# 16V3_EDA.net
KiCad netlist of a schematic drawn in EasyEDA Pro
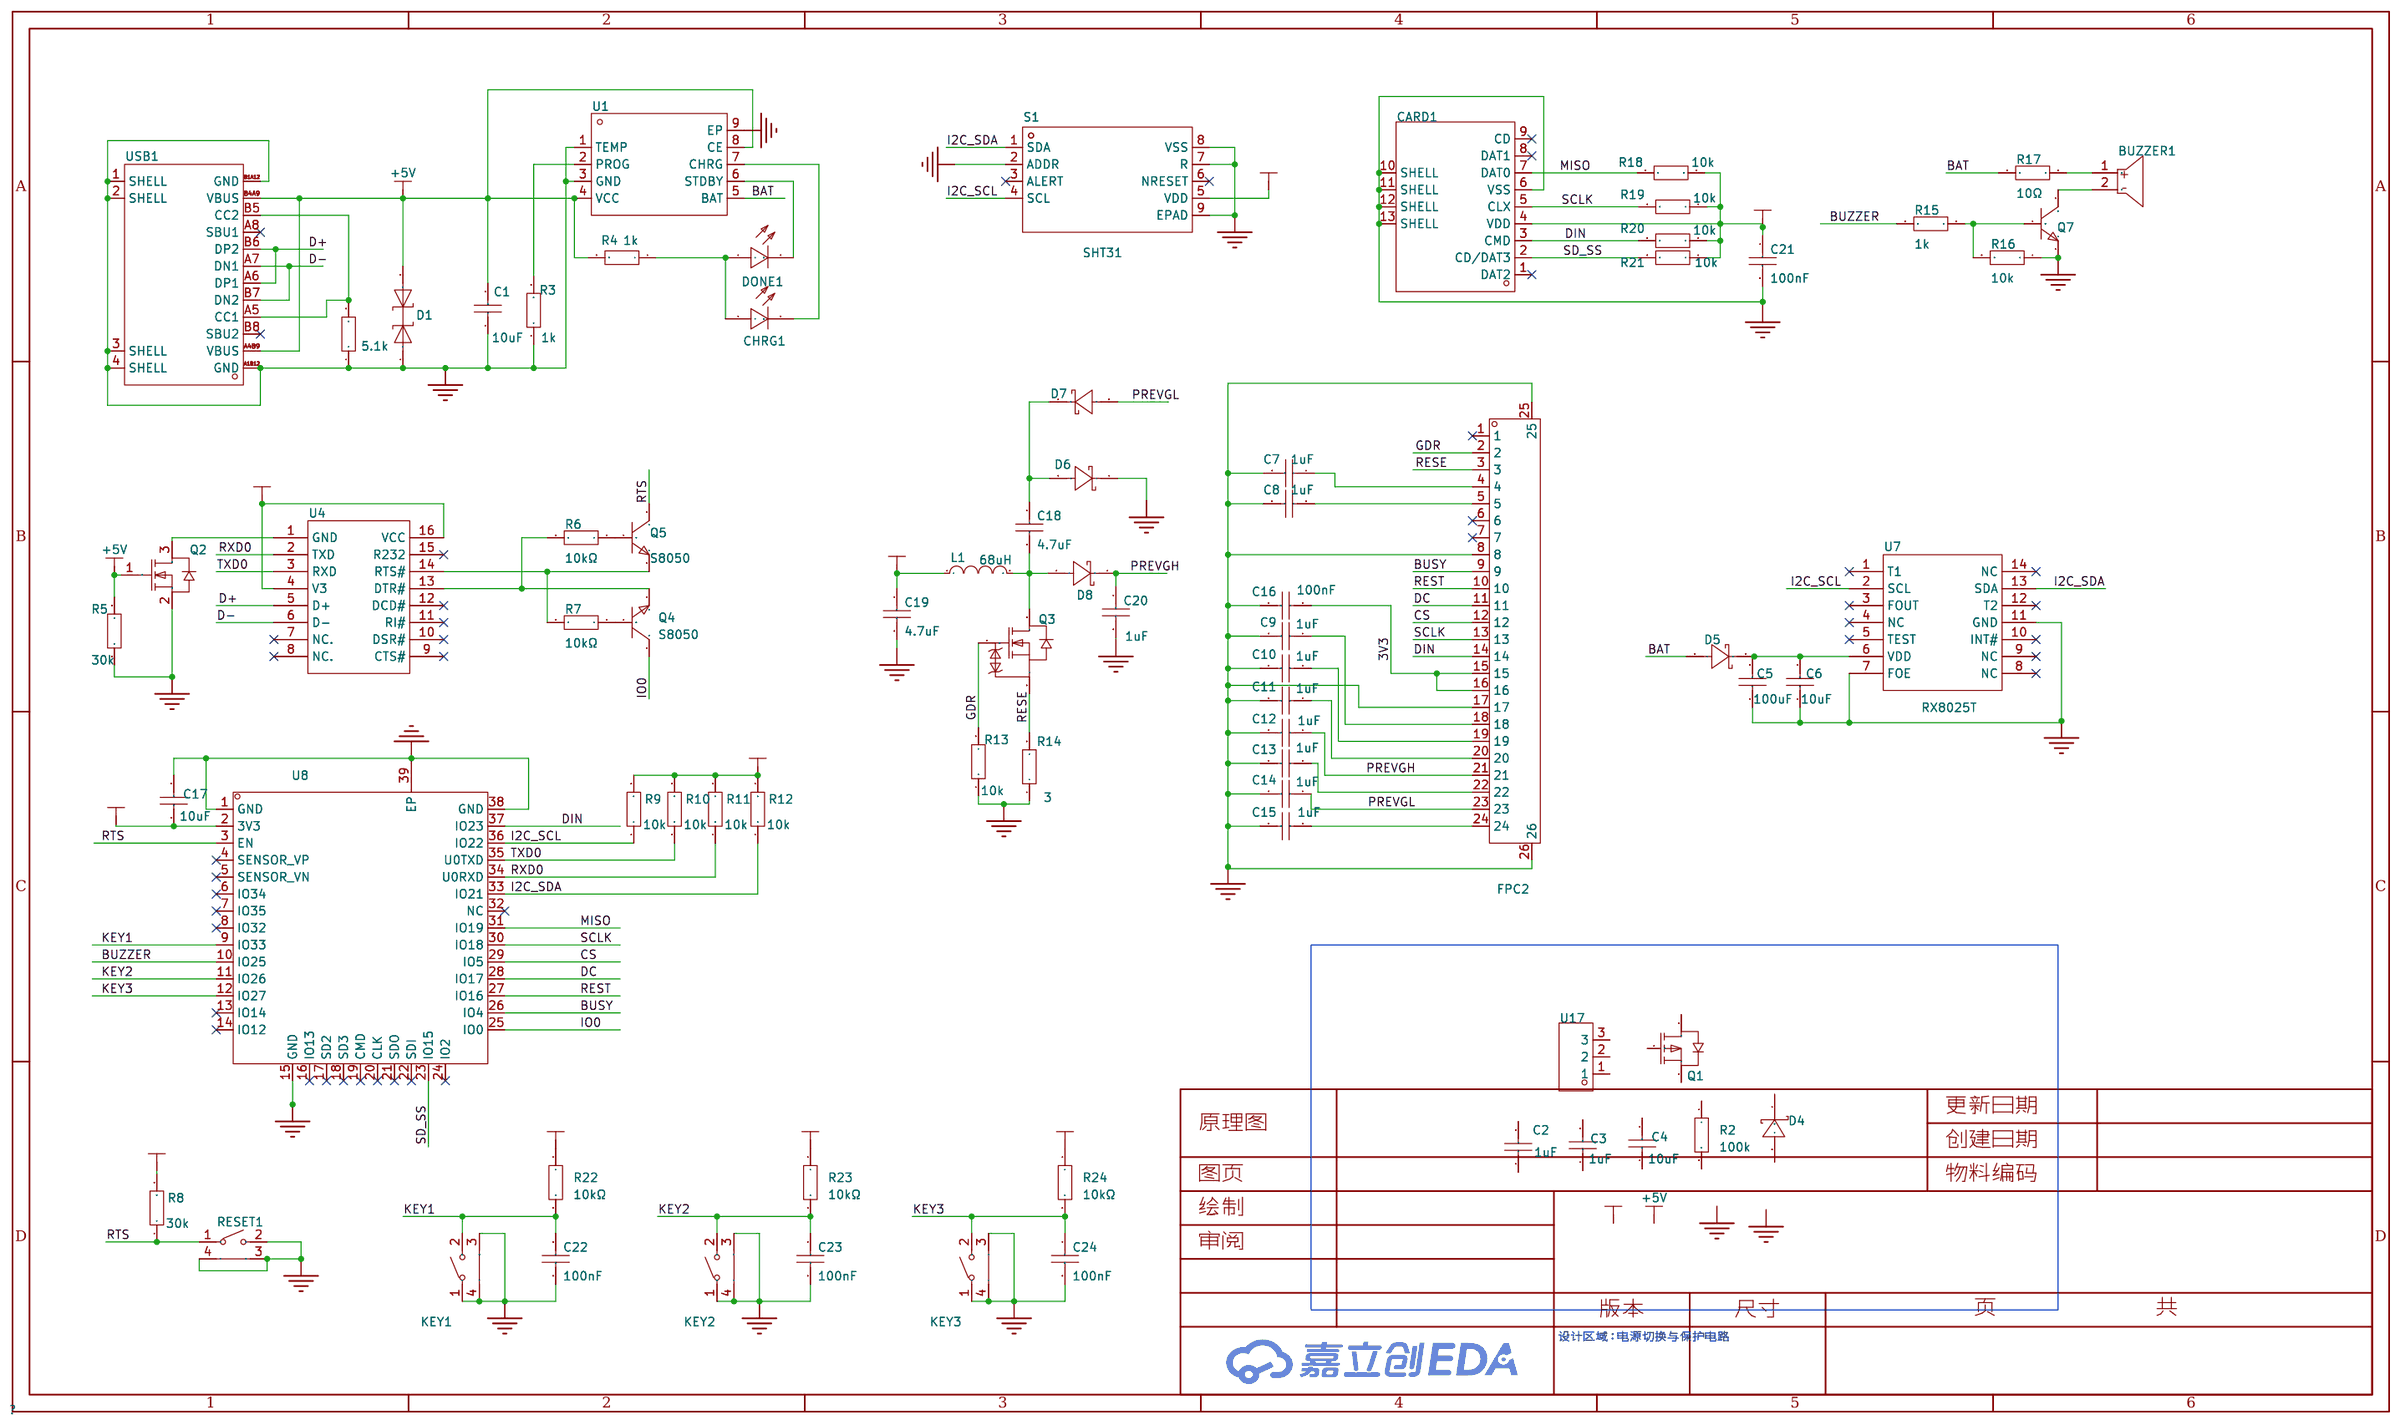
[diagram p0: schematic sheet]

(export (version "E")
  (design (tool "Eeschema 10.0.6"))
  (components
    (comp (ref "BUZZER1")
      (value "FMQ-BUZZER2")
      (footprint "easyedapro:BUZ-TH_BD12.0-P7.60-D0.6-FD")
      (libsource (lib "easyedapro") (part "FMQ-BUZZER2"))
    )
    (comp (ref "C1")
      (value "10uF")
      (footprint "easyedapro:C0805")
      (fields
        (field (name "Manufacturer Part") "CC0805KRX7R9BB104")
        (field (name "Manufacturer") "YAGEO(国巨)")
      )
      (libsource (lib "easyedapro") (part "CC0805KRX7R9BB104"))
    )
    (comp (ref "C2")
      (value "1uF")
      (footprint "easyedapro:C0805")
      (fields
        (field (name "Manufacturer Part") "CC0805KRX7R9BB104")
        (field (name "Manufacturer") "YAGEO(国巨)")
      )
      (libsource (lib "easyedapro") (part "CC0805KRX7R9BB104"))
    )
    (comp (ref "C3")
      (value "1uF")
      (footprint "easyedapro:C0805")
      (fields
        (field (name "Manufacturer Part") "CC0805KRX7R9BB104")
        (field (name "Manufacturer") "YAGEO(国巨)")
      )
      (libsource (lib "easyedapro") (part "CC0805KRX7R9BB104"))
    )
    (comp (ref "C4")
      (value "10uF")
      (footprint "easyedapro:C0805")
      (fields
        (field (name "Manufacturer Part") "CC0805KRX7R9BB104")
        (field (name "Manufacturer") "YAGEO(国巨)")
      )
      (libsource (lib "easyedapro") (part "CC0805KRX7R9BB104"))
    )
    (comp (ref "C5")
      (value "100uF")
      (footprint "easyedapro:C0805")
      (description "容值:100nF;精度:±10%;额定电压:50V;温度系数:X7R;")
      (fields
        (field (name "Manufacturer Part") "CC0805KRX7R9BB104")
        (field (name "Manufacturer") "YAGEO(国巨)")
      )
      (libsource (lib "easyedapro") (part "CC0805KRX7R9BB104"))
    )
    (comp (ref "C6")
      (value "10uF")
      (footprint "easyedapro:C0805")
      (fields
        (field (name "Manufacturer Part") "CC0805KRX7R9BB104")
        (field (name "Manufacturer") "YAGEO(国巨)")
      )
      (libsource (lib "easyedapro") (part "CC0805KRX7R9BB104"))
    )
    (comp (ref "C7")
      (value "1uF")
      (footprint "easyedapro:C0805")
      (fields
        (field (name "Manufacturer Part") "CC0805KRX7R9BB104")
        (field (name "Manufacturer") "YAGEO(国巨)")
      )
      (libsource (lib "easyedapro") (part "CC0805KRX7R9BB104"))
    )
    (comp (ref "C8")
      (value "1uF")
      (footprint "easyedapro:C0805")
      (fields
        (field (name "Manufacturer Part") "CC0805KRX7R9BB104")
        (field (name "Manufacturer") "YAGEO(国巨)")
      )
      (libsource (lib "easyedapro") (part "CC0805KRX7R9BB104"))
    )
    (comp (ref "C9")
      (value "1uF")
      (footprint "easyedapro:C0805")
      (fields
        (field (name "Manufacturer Part") "CC0805KRX7R9BB104")
        (field (name "Manufacturer") "YAGEO(国巨)")
      )
      (libsource (lib "easyedapro") (part "CC0805KRX7R9BB104"))
    )
    (comp (ref "C10")
      (value "1uF")
      (footprint "easyedapro:C0805")
      (fields
        (field (name "Manufacturer Part") "CC0805KRX7R9BB104")
        (field (name "Manufacturer") "YAGEO(国巨)")
      )
      (libsource (lib "easyedapro") (part "CC0805KRX7R9BB104"))
    )
    (comp (ref "C11")
      (value "1uF")
      (footprint "easyedapro:C0805")
      (fields
        (field (name "Manufacturer Part") "CC0805KRX7R9BB104")
        (field (name "Manufacturer") "YAGEO(国巨)")
      )
      (libsource (lib "easyedapro") (part "CC0805KRX7R9BB104"))
    )
    (comp (ref "C12")
      (value "1uF")
      (footprint "easyedapro:C0805")
      (fields
        (field (name "Manufacturer Part") "CC0805KRX7R9BB104")
        (field (name "Manufacturer") "YAGEO(国巨)")
      )
      (libsource (lib "easyedapro") (part "CC0805KRX7R9BB104"))
    )
    (comp (ref "C13")
      (value "1uF")
      (footprint "easyedapro:C0805")
      (fields
        (field (name "Manufacturer Part") "CC0805KRX7R9BB104")
        (field (name "Manufacturer") "YAGEO(国巨)")
      )
      (libsource (lib "easyedapro") (part "CC0805KRX7R9BB104"))
    )
    (comp (ref "C14")
      (value "1uF")
      (footprint "easyedapro:C0805")
      (fields
        (field (name "Manufacturer Part") "CC0805KRX7R9BB104")
        (field (name "Manufacturer") "YAGEO(国巨)")
      )
      (libsource (lib "easyedapro") (part "CC0805KRX7R9BB104"))
    )
    (comp (ref "C15")
      (value "1uF")
      (footprint "easyedapro:C0805")
      (fields
        (field (name "Manufacturer Part") "CC0805KRX7R9BB104")
        (field (name "Manufacturer") "YAGEO(国巨)")
      )
      (libsource (lib "easyedapro") (part "CC0805KRX7R9BB104"))
    )
    (comp (ref "C16")
      (value "100nF")
      (footprint "easyedapro:C0805")
      (description "容值:100nF;精度:±10%;额定电压:50V;温度系数:X7R;")
      (fields
        (field (name "Manufacturer Part") "CC0805KRX7R9BB104")
        (field (name "Manufacturer") "YAGEO(国巨)")
      )
      (libsource (lib "easyedapro") (part "CC0805KRX7R9BB104"))
    )
    (comp (ref "C17")
      (value "10uF")
      (footprint "easyedapro:C0805")
      (fields
        (field (name "Manufacturer Part") "CC0805KRX7R9BB104")
        (field (name "Manufacturer") "YAGEO(国巨)")
      )
      (libsource (lib "easyedapro") (part "CC0805KRX7R9BB104"))
    )
    (comp (ref "C18")
      (value "4.7uF")
      (footprint "easyedapro:C0805")
      (description "容值:100nF;精度:±10%;额定电压:50V;温度系数:X7R;")
      (fields
        (field (name "Manufacturer Part") "CC0805KRX7R9BB104")
        (field (name "Manufacturer") "YAGEO(国巨)")
      )
      (libsource (lib "easyedapro") (part "CC0805KRX7R9BB104"))
    )
    (comp (ref "C19")
      (value "4.7uF")
      (footprint "easyedapro:C0805")
      (fields
        (field (name "Manufacturer Part") "CC0805KRX7R9BB104")
        (field (name "Manufacturer") "YAGEO(国巨)")
      )
      (libsource (lib "easyedapro") (part "CC0805KRX7R9BB104"))
    )
    (comp (ref "C20")
      (value "1uF")
      (footprint "easyedapro:C0805")
      (fields
        (field (name "Manufacturer Part") "CC0805KRX7R9BB104")
        (field (name "Manufacturer") "YAGEO(国巨)")
      )
      (libsource (lib "easyedapro") (part "CC0805KRX7R9BB104"))
    )
    (comp (ref "C21")
      (value "100nF")
      (footprint "easyedapro:C0805")
      (description "容值:100nF;精度:±10%;额定电压:50V;温度系数:X7R;")
      (fields
        (field (name "Manufacturer Part") "CC0805KRX7R9BB104")
        (field (name "Manufacturer") "YAGEO(国巨)")
      )
      (libsource (lib "easyedapro") (part "CC0805KRX7R9BB104"))
    )
    (comp (ref "C22")
      (value "100nF")
      (footprint "easyedapro:C0805")
      (fields
        (field (name "Manufacturer Part") "CC0805KRX7R9BB104")
        (field (name "Manufacturer") "YAGEO(国巨)")
      )
      (libsource (lib "easyedapro") (part "CC0805KRX7R9BB104"))
    )
    (comp (ref "C23")
      (value "100nF")
      (footprint "easyedapro:C0805")
      (fields
        (field (name "Manufacturer Part") "CC0805KRX7R9BB104")
        (field (name "Manufacturer") "YAGEO(国巨)")
      )
      (libsource (lib "easyedapro") (part "CC0805KRX7R9BB104"))
    )
    (comp (ref "C24")
      (value "100nF")
      (footprint "easyedapro:C0805")
      (fields
        (field (name "Manufacturer Part") "CC0805KRX7R9BB104")
        (field (name "Manufacturer") "YAGEO(国巨)")
      )
      (libsource (lib "easyedapro") (part "CC0805KRX7R9BB104"))
    )
    (comp (ref "CARD1")
      (value "~")
      (footprint "easyedapro:TF-SMD_THD2528-11SD-GF")
      (description "卡连接方式:自弹式;卡类型:MicroSD卡(TF卡);连接器类型:卡座;本体最大高度:2mm;工作温度范围:-;")
      (fields (field (name "Manufacturer Part") "THD2528-11SD-GF") (field (name "Manufacturer") "THD(台华达)"))
      (libsource (lib "easyedapro") (part "THD2528-11SD-GF"))
    )
    (comp (ref "CHRG1")
      (value "~")
      (footprint "easyedapro:LED0603-R-RD")
      (fields
        (field (name "Manufacturer Part") "19-217/R6C-AL1M2VY/3T")
        (field (name "Manufacturer") "EVERLIGHT(台湾亿光)")
      )
      (libsource (lib "easyedapro") (part "19-217/R6C-AL1M2VY/3T"))
    )
    (comp (ref "D1")
      (value "~")
      (footprint "easyedapro:SOD-523_L1.2-W0.8-LS1.6-BI")
      (description "极性:双向;反向截止电压(Vrwm):5V@(最大值);击穿电压(最小值):5.6V;峰值脉冲电流(Ipp)@10/1000s:4A;最大钳位电压:12V;")
      (fields (field (name "Manufacturer Part") "ESD5Z5.0VC") (field (name "Manufacturer") "TC(德昌)"))
      (libsource (lib "easyedapro") (part "ESD5Z5.0VC"))
    )
    (comp (ref "D4")
      (value "~")
      (footprint "easyedapro:SMA_L4.3-W2.6-LS5.1-RD")
      (description "直流反向耐压(Vr):40V;平均整流电流(Io):3A;正向压降(Vf):550mV@3A;")
      (fields (field (name "Manufacturer Part") "SS34") (field (name "Manufacturer") "SINO-IC(光宇睿芯)"))
      (libsource (lib "easyedapro") (part "SS34_C355267"))
    )
    (comp (ref "D5")
      (value "~")
      (footprint "easyedapro:SOD-123_L2.7-W1.6-LS3.7-RD-1")
      (description "直流反向耐压(Vr):30V;平均整流电流(Io):500mA;正向压降(Vf):550mV@500mA;")
      (fields (field (name "Manufacturer Part") "MBR0530") (field (name "Manufacturer") "YANGJIE(扬杰)"))
      (libsource (lib "easyedapro") (part "MBR0530_C699108"))
    )
    (comp (ref "D6")
      (value "~")
      (footprint "easyedapro:SOD-123_L2.7-W1.6-LS3.7-RD-1")
      (description "直流反向耐压(Vr):30V;平均整流电流(Io):500mA;正向压降(Vf):550mV@500mA;")
      (fields (field (name "Manufacturer Part") "MBR0530") (field (name "Manufacturer") "YANGJIE(扬杰)"))
      (libsource (lib "easyedapro") (part "MBR0530_C699108"))
    )
    (comp (ref "D7")
      (value "~")
      (footprint "easyedapro:SOD-123_L2.7-W1.6-LS3.7-RD-1")
      (description "直流反向耐压(Vr):30V;平均整流电流(Io):500mA;正向压降(Vf):550mV@500mA;")
      (fields (field (name "Manufacturer Part") "MBR0530") (field (name "Manufacturer") "YANGJIE(扬杰)"))
      (libsource (lib "easyedapro") (part "MBR0530_C699108"))
    )
    (comp (ref "D8")
      (value "~")
      (footprint "easyedapro:SOD-123_L2.7-W1.6-LS3.7-RD-1")
      (description "直流反向耐压(Vr):30V;平均整流电流(Io):500mA;正向压降(Vf):550mV@500mA;")
      (fields (field (name "Manufacturer Part") "MBR0530") (field (name "Manufacturer") "YANGJIE(扬杰)"))
      (libsource (lib "easyedapro") (part "MBR0530_C699108"))
    )
    (comp (ref "DONE1")
      (value "~")
      (footprint "easyedapro:LED0603-R-RD")
      (fields
        (field (name "Manufacturer Part") "19-217/R6C-AL1M2VY/3T")
        (field (name "Manufacturer") "EVERLIGHT(台湾亿光)")
      )
      (libsource (lib "easyedapro") (part "19-217/R6C-AL1M2VY/3T"))
    )
    (comp (ref "FPC2")
      (value "~")
      (footprint "easyedapro:FPC-SMD_24P-L17.5-W5.4-P0.50")
      (description "间距:0.5mm;触点数量:24;锁定特性:抽屉式;安装类型:卧贴;触点类型:上接;")
      (fields (field (name "Manufacturer Part") "AFC07-S24ECC-00") (field (name "Manufacturer") "JS(钜硕电子)"))
      (libsource (lib "easyedapro") (part "FPC 0.5MM 24P Pull type H2.0mm Pick up"))
    )
    (comp (ref "KEY1")
      (value "~")
      (footprint "easyedapro:SW-SMD_L4.7-W3.5-P3.35-EH")
      (fields
        (field (name "Manufacturer Part") "GT-TC018B-H0375-L1")
        (field (name "Manufacturer") "G-Switch(品赞)")
      )
      (libsource (lib "easyedapro") (part "GT-TC018B-H0375-L1"))
    )
    (comp (ref "KEY2")
      (value "~")
      (footprint "easyedapro:SW-SMD_L4.7-W3.5-P3.35-EH")
      (fields
        (field (name "Manufacturer Part") "GT-TC018B-H0375-L1")
        (field (name "Manufacturer") "G-Switch(品赞)")
      )
      (libsource (lib "easyedapro") (part "GT-TC018B-H0375-L1"))
    )
    (comp (ref "KEY3")
      (value "~")
      (footprint "easyedapro:SW-SMD_L4.7-W3.5-P3.35-EH")
      (fields
        (field (name "Manufacturer Part") "GT-TC018B-H0375-L1")
        (field (name "Manufacturer") "G-Switch(品赞)")
      )
      (libsource (lib "easyedapro") (part "GT-TC018B-H0375-L1"))
    )
    (comp (ref "L1")
      (value "68uH")
      (footprint "easyedapro:IND-SMD_L4.0-W4.0")
      (description "电感值:68uH;精度:±20%;额定电流:-;直流电阻(DCR):-;")
      (fields (field (name "Manufacturer Part") "CR4020-680M") (field (name "Manufacturer") "ceaiya(柯爱亚)"))
      (libsource (lib "easyedapro") (part "CR4020-680M"))
    )
    (comp (ref "Q1")
      (value "~")
      (footprint "easyedapro:SOT-23_L2.9-W1.3-P1.90-LS2.4-BR")
      (fields (field (name "Manufacturer Part") "SI2305") (field (name "Manufacturer") "BORN伯恩半导体"))
      (libsource (lib "easyedapro") (part "SI2305_C344006"))
    )
    (comp (ref "Q2")
      (value "~")
      (footprint "easyedapro:SOT-23_L2.9-W1.3-P1.90-LS2.4-BR")
      (fields (field (name "Manufacturer Part") "AO3402") (field (name "Manufacturer") "GOODWORK(固得沃克)"))
      (libsource (lib "easyedapro") (part "AO3402_C2938369"))
    )
    (comp (ref "Q3")
      (value "~")
      (footprint "easyedapro:SOT-323_L2.0-W1.3-P1.30-LS2.1-BR")
      (fields
        (field (name "Manufacturer Part") "SI1308EDL-T1-GE3")
        (field (name "Manufacturer") "VISHAY(威世)")
      )
      (libsource (lib "easyedapro") (part "SI1308EDL-T1-GE3"))
    )
    (comp (ref "Q4")
      (value "S8050")
      (footprint "easyedapro:SOT-23-3_L3.0-W1.7-P0.95-LS2.9-BR")
      (fields (field (name "Manufacturer") "CJ"))
      (libsource (lib "easyedapro") (part "S8050"))
    )
    (comp (ref "Q5")
      (value "S8050")
      (footprint "easyedapro:SOT-23-3_L3.0-W1.7-P0.95-LS2.9-BR(1)")
      (fields (field (name "Manufacturer") "CJ"))
      (libsource (lib "") (part "S8050_1"))
    )
    (comp (ref "Q7")
      (value "S8050-J3Y")
      (footprint "easyedapro:SOT-23-3_L3.0-W1.7-P0.95-LS2.9-BR")
      (fields (field (name "Manufacturer") "(MDD) Jiangsu Yutai Elec"))
      (libsource (lib "easyedapro") (part "S8050-J3Y"))
    )
    (comp (ref "R1")
      (value "5.1k")
      (footprint "easyedapro:R0603")
      (description "电阻类型:薄膜电阻;阻值:10k;精度:±0.1%;功率:100mW;温度系数:±25ppm/;最大工作电压:75V;工作温度范围:-55~+155;")
      (fields
        (field (name "Manufacturer Part") "TR0603B10K0P0525Z")
        (field (name "Manufacturer") "EVER OHMS(天二科技)")
      )
      (libsource (lib "easyedapro") (part "TR0603B10KP05250.1W"))
    )
    (comp (ref "R2")
      (value "100k")
      (footprint "easyedapro:R0603")
      (description "电阻类型:薄膜电阻;阻值:10k;精度:±0.1%;功率:100mW;温度系数:±25ppm/;最大工作电压:75V;工作温度范围:-55~+155;")
      (fields
        (field (name "Manufacturer Part") "TR0603B10K0P0525Z")
        (field (name "Manufacturer") "EVER OHMS(天二科技)")
      )
      (libsource (lib "easyedapro") (part "TR0603B10KP05250.1W"))
    )
    (comp (ref "R3")
      (value "1k")
      (footprint "easyedapro:R0603")
      (description "电阻类型:薄膜电阻;阻值:10k;精度:±0.1%;功率:100mW;温度系数:±25ppm/;最大工作电压:75V;工作温度范围:-55~+155;")
      (fields
        (field (name "Manufacturer Part") "TR0603B10K0P0525Z")
        (field (name "Manufacturer") "EVER OHMS(天二科技)")
      )
      (libsource (lib "easyedapro") (part "TR0603B10KP05250.1W"))
    )
    (comp (ref "R4")
      (value "1k")
      (footprint "easyedapro:R0603")
      (description "电阻类型:薄膜电阻;阻值:10k;精度:±0.1%;功率:100mW;温度系数:±25ppm/;最大工作电压:75V;工作温度范围:-55~+155;")
      (fields
        (field (name "Manufacturer Part") "TR0603B10K0P0525Z")
        (field (name "Manufacturer") "EVER OHMS(天二科技)")
      )
      (libsource (lib "easyedapro") (part "TR0603B10KP05250.1W"))
    )
    (comp (ref "R5")
      (value "30k")
      (footprint "easyedapro:R0603")
      (description "电阻类型:薄膜电阻;阻值:10k;精度:±0.1%;功率:100mW;温度系数:±25ppm/;最大工作电压:75V;工作温度范围:-55~+155;")
      (fields
        (field (name "Manufacturer Part") "TR0603B10K0P0525Z")
        (field (name "Manufacturer") "EVER OHMS(天二科技)")
      )
      (libsource (lib "easyedapro") (part "TR0603B10KP05250.1W"))
    )
    (comp (ref "R6")
      (value "10kΩ")
      (footprint "easyedapro:R0603")
      (description "电阻类型:薄膜电阻;阻值:10k;精度:±0.1%;功率:100mW;温度系数:±25ppm/;最大工作电压:75V;工作温度范围:-55~+155;")
      (fields
        (field (name "Manufacturer Part") "TR0603B10K0P0525Z")
        (field (name "Manufacturer") "EVER OHMS(天二科技)")
      )
      (libsource (lib "easyedapro") (part "TR0603B10KP05250.1W"))
    )
    (comp (ref "R7")
      (value "10kΩ")
      (footprint "easyedapro:R0603")
      (description "电阻类型:薄膜电阻;阻值:10k;精度:±0.1%;功率:100mW;温度系数:±25ppm/;最大工作电压:75V;工作温度范围:-55~+155;")
      (fields
        (field (name "Manufacturer Part") "TR0603B10K0P0525Z")
        (field (name "Manufacturer") "EVER OHMS(天二科技)")
      )
      (libsource (lib "easyedapro") (part "TR0603B10KP05250.1W"))
    )
    (comp (ref "R8")
      (value "30k")
      (footprint "easyedapro:R0603")
      (description "电阻类型:薄膜电阻;阻值:10k;精度:±0.1%;功率:100mW;温度系数:±25ppm/;最大工作电压:75V;工作温度范围:-55~+155;")
      (fields
        (field (name "Manufacturer Part") "TR0603B10K0P0525Z")
        (field (name "Manufacturer") "EVER OHMS(天二科技)")
      )
      (libsource (lib "easyedapro") (part "TR0603B10KP05250.1W"))
    )
    (comp (ref "R9")
      (value "10k")
      (footprint "easyedapro:R0603")
      (description "电阻类型:薄膜电阻;阻值:10k;精度:±0.1%;功率:100mW;温度系数:±25ppm/;最大工作电压:75V;工作温度范围:-55~+155;")
      (fields
        (field (name "Manufacturer Part") "TR0603B10K0P0525Z")
        (field (name "Manufacturer") "EVER OHMS(天二科技)")
      )
      (libsource (lib "easyedapro") (part "TR0603B10KP05250.1W"))
    )
    (comp (ref "R10")
      (value "10k")
      (footprint "easyedapro:R0603")
      (description "电阻类型:薄膜电阻;阻值:10k;精度:±0.1%;功率:100mW;温度系数:±25ppm/;最大工作电压:75V;工作温度范围:-55~+155;")
      (fields
        (field (name "Manufacturer Part") "TR0603B10K0P0525Z")
        (field (name "Manufacturer") "EVER OHMS(天二科技)")
      )
      (libsource (lib "easyedapro") (part "TR0603B10KP05250.1W"))
    )
    (comp (ref "R11")
      (value "10k")
      (footprint "easyedapro:R0603")
      (description "电阻类型:薄膜电阻;阻值:10k;精度:±0.1%;功率:100mW;温度系数:±25ppm/;最大工作电压:75V;工作温度范围:-55~+155;")
      (fields
        (field (name "Manufacturer Part") "TR0603B10K0P0525Z")
        (field (name "Manufacturer") "EVER OHMS(天二科技)")
      )
      (libsource (lib "easyedapro") (part "TR0603B10KP05250.1W"))
    )
    (comp (ref "R12")
      (value "10k")
      (footprint "easyedapro:R0603")
      (description "电阻类型:薄膜电阻;阻值:10k;精度:±0.1%;功率:100mW;温度系数:±25ppm/;最大工作电压:75V;工作温度范围:-55~+155;")
      (fields
        (field (name "Manufacturer Part") "TR0603B10K0P0525Z")
        (field (name "Manufacturer") "EVER OHMS(天二科技)")
      )
      (libsource (lib "easyedapro") (part "TR0603B10KP05250.1W"))
    )
    (comp (ref "R13")
      (value "10k")
      (footprint "easyedapro:R0603")
      (description "电阻类型:薄膜电阻;阻值:10k;精度:±0.1%;功率:100mW;温度系数:±25ppm/;最大工作电压:75V;工作温度范围:-55~+155;")
      (fields
        (field (name "Manufacturer Part") "TR0603B10K0P0525Z")
        (field (name "Manufacturer") "EVER OHMS(天二科技)")
      )
      (libsource (lib "easyedapro") (part "TR0603B10KP05250.1W"))
    )
    (comp (ref "R14")
      (value "3")
      (footprint "easyedapro:R0603")
      (description "电阻类型:薄膜电阻;阻值:10k;精度:±0.1%;功率:100mW;温度系数:±25ppm/;最大工作电压:75V;工作温度范围:-55~+155;")
      (fields
        (field (name "Manufacturer Part") "TR0603B10K0P0525Z")
        (field (name "Manufacturer") "EVER OHMS(天二科技)")
      )
      (libsource (lib "easyedapro") (part "TR0603B10KP05250.1W"))
    )
    (comp (ref "R15")
      (value "1k")
      (footprint "easyedapro:R0603")
      (description "电阻类型:薄膜电阻;阻值:10k;精度:±0.1%;功率:100mW;温度系数:±25ppm/;最大工作电压:75V;工作温度范围:-55~+155;")
      (fields
        (field (name "Manufacturer Part") "TR0603B10K0P0525Z")
        (field (name "Manufacturer") "EVER OHMS(天二科技)")
      )
      (libsource (lib "easyedapro") (part "TR0603B10KP05250.1W"))
    )
    (comp (ref "R16")
      (value "10k")
      (footprint "easyedapro:R0603")
      (description "电阻类型:薄膜电阻;阻值:10k;精度:±0.1%;功率:100mW;温度系数:±25ppm/;最大工作电压:75V;工作温度范围:-55~+155;")
      (fields
        (field (name "Manufacturer Part") "TR0603B10K0P0525Z")
        (field (name "Manufacturer") "EVER OHMS(天二科技)")
      )
      (libsource (lib "easyedapro") (part "TR0603B10KP05250.1W"))
    )
    (comp (ref "R17")
      (value "10Ω")
      (footprint "easyedapro:R0603")
      (description "电阻类型:厚膜电阻;阻值:10Ω;精度:±1%;功率:100mW;")
      (fields
        (field (name "Manufacturer Part") "0603WAF100JT5E")
        (field (name "Manufacturer") "UNI-ROYAL(厚声)")
      )
      (libsource (lib "easyedapro") (part "0603WAF100JT5E"))
    )
    (comp (ref "R18")
      (value "10k")
      (footprint "easyedapro:R0603")
      (description "电阻类型:薄膜电阻;阻值:10k;精度:±0.1%;功率:100mW;温度系数:±25ppm/;最大工作电压:75V;工作温度范围:-55~+155;")
      (fields
        (field (name "Manufacturer Part") "TR0603B10K0P0525Z")
        (field (name "Manufacturer") "EVER OHMS(天二科技)")
      )
      (libsource (lib "easyedapro") (part "TR0603B10KP05250.1W"))
    )
    (comp (ref "R19")
      (value "10k")
      (footprint "easyedapro:R0603")
      (description "电阻类型:薄膜电阻;阻值:10k;精度:±0.1%;功率:100mW;温度系数:±25ppm/;最大工作电压:75V;工作温度范围:-55~+155;")
      (fields
        (field (name "Manufacturer Part") "TR0603B10K0P0525Z")
        (field (name "Manufacturer") "EVER OHMS(天二科技)")
      )
      (libsource (lib "easyedapro") (part "TR0603B10KP05250.1W"))
    )
    (comp (ref "R20")
      (value "10k")
      (footprint "easyedapro:R0603")
      (description "电阻类型:薄膜电阻;阻值:10k;精度:±0.1%;功率:100mW;温度系数:±25ppm/;最大工作电压:75V;工作温度范围:-55~+155;")
      (fields
        (field (name "Manufacturer Part") "TR0603B10K0P0525Z")
        (field (name "Manufacturer") "EVER OHMS(天二科技)")
      )
      (libsource (lib "easyedapro") (part "TR0603B10KP05250.1W"))
    )
    (comp (ref "R21")
      (value "10k")
      (footprint "easyedapro:R0603")
      (description "电阻类型:薄膜电阻;阻值:10k;精度:±0.1%;功率:100mW;温度系数:±25ppm/;最大工作电压:75V;工作温度范围:-55~+155;")
      (fields
        (field (name "Manufacturer Part") "TR0603B10K0P0525Z")
        (field (name "Manufacturer") "EVER OHMS(天二科技)")
      )
      (libsource (lib "easyedapro") (part "TR0603B10KP05250.1W"))
    )
    (comp (ref "R22")
      (value "10kΩ")
      (footprint "easyedapro:R0603")
      (description "电阻类型:薄膜电阻;阻值:10k;精度:±0.1%;功率:100mW;温度系数:±25ppm/;最大工作电压:75V;工作温度范围:-55~+155;")
      (fields
        (field (name "Manufacturer Part") "TR0603B10K0P0525Z")
        (field (name "Manufacturer") "EVER OHMS(天二科技)")
      )
      (libsource (lib "easyedapro") (part "TR0603B10KP05250.1W"))
    )
    (comp (ref "R23")
      (value "10kΩ")
      (footprint "easyedapro:R0603")
      (description "电阻类型:薄膜电阻;阻值:10k;精度:±0.1%;功率:100mW;温度系数:±25ppm/;最大工作电压:75V;工作温度范围:-55~+155;")
      (fields
        (field (name "Manufacturer Part") "TR0603B10K0P0525Z")
        (field (name "Manufacturer") "EVER OHMS(天二科技)")
      )
      (libsource (lib "easyedapro") (part "TR0603B10KP05250.1W"))
    )
    (comp (ref "R24")
      (value "10kΩ")
      (footprint "easyedapro:R0603")
      (description "电阻类型:薄膜电阻;阻值:10k;精度:±0.1%;功率:100mW;温度系数:±25ppm/;最大工作电压:75V;工作温度范围:-55~+155;")
      (fields
        (field (name "Manufacturer Part") "TR0603B10K0P0525Z")
        (field (name "Manufacturer") "EVER OHMS(天二科技)")
      )
      (libsource (lib "easyedapro") (part "TR0603B10KP05250.1W"))
    )
    (comp (ref "RESET1")
      (value "~")
      (footprint "easyedapro:SW-SMD_L4.7-W3.5-P3.35-EH")
      (fields
        (field (name "Manufacturer Part") "GT-TC018B-H0375-L1")
        (field (name "Manufacturer") "G-Switch(品赞)")
      )
      (libsource (lib "easyedapro") (part "GT-TC018B-H0375-L1"))
    )
    (comp (ref "S1")
      (value "SHT31")
      (footprint "easyedapro:DFN-8_L2.5-W2.5-P0.50-BL-EP")
      (description "1-101386-01")
      (fields (field (name "Manufacturer") "Sensirion(瑞士盛思锐)"))
      (libsource (lib "easyedapro") (part "SHT31-DIS-B"))
    )
    (comp (ref "U1")
      (value "~")
      (footprint "easyedapro:ESOP-8_L4.9-W3.9-P1.27-LS6.0-BL-EP")
      (description "充电电池的类型:-;电池单元组数:-;最大充电电流:-;充满的电池组电压:-;最大供应电压:-;")
      (fields (field (name "Manufacturer Part") "TP4056") (field (name "Manufacturer") "UMW(友台半导体)"))
      (libsource (lib "easyedapro") (part "TP4056_C725790"))
    )
    (comp (ref "U4")
      (value "~")
      (footprint "easyedapro:SOP-16_L10.0-W3.9-P1.27-LS6.0-BL")
      (description "类型:Transceiver;协议类别:USB 2.0;驱动器/接收器数:-;数据速率:2Mbps;")
      (fields (field (name "Manufacturer Part") "CH340C") (field (name "Manufacturer") "WCH(南京沁恒)"))
      (libsource (lib "easyedapro") (part "CH340C"))
    )
    (comp (ref "U7")
      (value "RX8025T")
      (footprint "easyedapro:SOIC-14_L10.0-W5.5-P1.27-LS7.8-BL")
      (description "时钟芯片类型:Clock/Calendar;存储器容量:-;时间格式:HH:MM:SS;日期格式:YY-MM-DD;接口类型:I2C;")
      (fields (field (name "Manufacturer Part") "RX8025T-UB") (field (name "Manufacturer") "EPSON(爱普生)"))
      (libsource (lib "easyedapro") (part "RX8025T-UB"))
    )
    (comp (ref "U8")
      (value "~")
      (footprint "easyedapro:WIRELM-SMD_ESP32-S")
      (fields (field (name "Manufacturer Part") "ESP32-S") (field (name "Manufacturer") "Ai-Thinker(安信可)"))
      (libsource (lib "easyedapro") (part "ESP32-S"))
    )
    (comp (ref "U17")
      (value "ZX-XH2.54-3PZZ")
      (footprint "easyedapro:CONN-TH_3P-P2.54_2501S-3P")
      (fields (field (name "Manufacturer") "Megastar(兆星)"))
      (libsource (lib "easyedapro") (part "ZX-XH2.54-3PZZ"))
    )
    (comp (ref "USB1")
      (value "~")
      (footprint "easyedapro:USB-SMD_TYPE-611S-T3")
      (description "连接器类型:Type-C;标准:-;公母:母座;触点数量:16;端口数量:1;安装方式:卧贴;额定电流 - 电源:3A;工作温度范围:-25~+85;")
      (fields (field (name "Manufacturer Part") "TYPE-611S-T3") (field (name "Manufacturer") "Yuandi(台湾元迪)"))
      (libsource (lib "easyedapro") (part "TYPE-611S-T3"))
    )
  )
  (nets
    (net (code "1") (name "+5V") (class "Default")
      (node (ref "C1") (pin "2") (pinfunction "2_2") (pintype "input"))
      (node (ref "D1") (pin "2") (pinfunction "2_2") (pintype "input"))
      (node (ref "Q2") (pin "1") (pinfunction "G_1") (pintype "input"))
      (node (ref "R4") (pin "2") (pinfunction "2_2") (pintype "input"))
      (node (ref "R5") (pin "2") (pinfunction "2_2") (pintype "input"))
      (node (ref "U1") (pin "4") (pinfunction "VCC_4") (pintype "input"))
      (node (ref "U1") (pin "8") (pinfunction "CE_8") (pintype "input"))
      (node (ref "USB1") (pin "A4B9") (pinfunction "VBUS_A4B9") (pintype "input"))
      (node (ref "USB1") (pin "B4A9") (pinfunction "VBUS_B4A9") (pintype "input"))
    )
    (net (code "2") (name "/BAT") (class "Default")
      (node (ref "D5") (pin "2") (pinfunction "A_2") (pintype "input"))
      (node (ref "R17") (pin "1") (pinfunction "1_1") (pintype "input"))
      (node (ref "U1") (pin "5") (pinfunction "BAT_5") (pintype "input"))
    )
    (net (code "3") (name "/BUSY") (class "Default")
      (node (ref "FPC2") (pin "9") (pinfunction "9_9") (pintype "input"))
      (node (ref "U8") (pin "26") (pinfunction "IO4_26") (pintype "input"))
    )
    (net (code "4") (name "/BUZZER") (class "Default")
      (node (ref "R15") (pin "2") (pinfunction "2_2") (pintype "input"))
      (node (ref "U8") (pin "10") (pinfunction "IO25_10") (pintype "input"))
    )
    (net (code "5") (name "/CS") (class "Default")
      (node (ref "FPC2") (pin "12") (pinfunction "12_12") (pintype "input"))
      (node (ref "U8") (pin "29") (pinfunction "IO5_29") (pintype "input"))
    )
    (net (code "6") (name "/D+") (class "Default")
      (node (ref "U4") (pin "5") (pinfunction "D+_5") (pintype "input"))
      (node (ref "USB1") (pin "A6") (pinfunction "DP1_A6") (pintype "input"))
      (node (ref "USB1") (pin "B6") (pinfunction "DP2_B6") (pintype "input"))
    )
    (net (code "7") (name "/D-") (class "Default")
      (node (ref "U4") (pin "6") (pinfunction "D-_6") (pintype "input"))
      (node (ref "USB1") (pin "A7") (pinfunction "DN1_A7") (pintype "input"))
      (node (ref "USB1") (pin "B7") (pinfunction "DN2_B7") (pintype "input"))
    )
    (net (code "8") (name "/DC") (class "Default")
      (node (ref "FPC2") (pin "11") (pinfunction "11_11") (pintype "input"))
      (node (ref "U8") (pin "28") (pinfunction "IO17_28") (pintype "input"))
    )
    (net (code "9") (name "/DIN") (class "Default")
      (node (ref "CARD1") (pin "3") (pinfunction "CMD_3") (pintype "input"))
      (node (ref "FPC2") (pin "14") (pinfunction "14_14") (pintype "input"))
      (node (ref "R20") (pin "2") (pinfunction "2_2") (pintype "input"))
      (node (ref "U8") (pin "37") (pinfunction "IO23_37") (pintype "input"))
    )
    (net (code "10") (name "/GDR") (class "Default")
      (node (ref "FPC2") (pin "2") (pinfunction "2_2") (pintype "input"))
      (node (ref "Q3") (pin "1") (pinfunction "G_1") (pintype "input"))
      (node (ref "R13") (pin "2") (pinfunction "2_2") (pintype "input"))
    )
    (net (code "11") (name "/I2C_SCL") (class "Default")
      (node (ref "R9") (pin "1") (pinfunction "1_1") (pintype "input"))
      (node (ref "S1") (pin "4") (pinfunction "SCL_4") (pintype "unspecified"))
      (node (ref "U7") (pin "2") (pinfunction "SCL_2") (pintype "input"))
      (node (ref "U8") (pin "36") (pinfunction "IO22_36") (pintype "input"))
    )
    (net (code "12") (name "/I2C_SDA") (class "Default")
      (node (ref "R12") (pin "1") (pinfunction "1_1") (pintype "input"))
      (node (ref "S1") (pin "1") (pinfunction "SDA_1") (pintype "unspecified"))
      (node (ref "U7") (pin "13") (pinfunction "SDA_13") (pintype "input"))
      (node (ref "U8") (pin "33") (pinfunction "IO21_33") (pintype "input"))
    )
    (net (code "13") (name "/IO0") (class "Default")
      (node (ref "Q4") (pin "3") (pinfunction "C_3") (pintype "input"))
      (node (ref "U8") (pin "25") (pinfunction "IO0_25") (pintype "input"))
    )
    (net (code "14") (name "/KEY1") (class "Default")
      (node (ref "C22") (pin "1") (pinfunction "1_1") (pintype "input"))
      (node (ref "KEY1") (pin "2") (pinfunction "2_2") (pintype "input"))
      (node (ref "R22") (pin "2") (pinfunction "2_2") (pintype "input"))
      (node (ref "U8") (pin "9") (pinfunction "IO33_9") (pintype "input"))
    )
    (net (code "15") (name "/KEY2") (class "Default")
      (node (ref "C23") (pin "1") (pinfunction "1_1") (pintype "input"))
      (node (ref "KEY2") (pin "2") (pinfunction "2_2") (pintype "input"))
      (node (ref "R23") (pin "2") (pinfunction "2_2") (pintype "input"))
      (node (ref "U8") (pin "11") (pinfunction "IO26_11") (pintype "input"))
    )
    (net (code "16") (name "/KEY3") (class "Default")
      (node (ref "C24") (pin "1") (pinfunction "1_1") (pintype "input"))
      (node (ref "KEY3") (pin "2") (pinfunction "2_2") (pintype "input"))
      (node (ref "R24") (pin "2") (pinfunction "2_2") (pintype "input"))
      (node (ref "U8") (pin "12") (pinfunction "IO27_12") (pintype "input"))
    )
    (net (code "17") (name "/MISO") (class "Default")
      (node (ref "CARD1") (pin "7") (pinfunction "DAT0_7") (pintype "input"))
      (node (ref "R18") (pin "2") (pinfunction "2_2") (pintype "input"))
      (node (ref "U8") (pin "31") (pinfunction "IO19_31") (pintype "input"))
    )
    (net (code "18") (name "/PREVGH") (class "Default")
      (node (ref "C12") (pin "1") (pinfunction "1_1") (pintype "input"))
      (node (ref "C20") (pin "1") (pinfunction "1_1") (pintype "input"))
      (node (ref "D8") (pin "1") (pinfunction "K_1") (pintype "input"))
      (node (ref "FPC2") (pin "21") (pinfunction "21_21") (pintype "input"))
    )
    (net (code "19") (name "/PREVGL") (class "Default")
      (node (ref "C14") (pin "1") (pinfunction "1_1") (pintype "input"))
      (node (ref "D7") (pin "2") (pinfunction "A_2") (pintype "input"))
      (node (ref "FPC2") (pin "23") (pinfunction "23_23") (pintype "input"))
    )
    (net (code "20") (name "/RESE") (class "Default")
      (node (ref "FPC2") (pin "3") (pinfunction "3_3") (pintype "input"))
      (node (ref "Q3") (pin "2") (pinfunction "S_2") (pintype "input"))
      (node (ref "R14") (pin "2") (pinfunction "2_2") (pintype "input"))
    )
    (net (code "21") (name "/REST") (class "Default")
      (node (ref "FPC2") (pin "10") (pinfunction "10_10") (pintype "input"))
      (node (ref "U8") (pin "27") (pinfunction "IO16_27") (pintype "input"))
    )
    (net (code "22") (name "/RTS") (class "Default")
      (node (ref "Q5") (pin "3") (pinfunction "C_3") (pintype "input"))
      (node (ref "R8") (pin "1") (pinfunction "1_1") (pintype "input"))
      (node (ref "RESET1") (pin "1") (pinfunction "1_1") (pintype "input"))
      (node (ref "U8") (pin "3") (pinfunction "EN_3") (pintype "input"))
    )
    (net (code "23") (name "/RXD0") (class "Default")
      (node (ref "R11") (pin "1") (pinfunction "1_1") (pintype "input"))
      (node (ref "U4") (pin "2") (pinfunction "TXD_2") (pintype "input"))
      (node (ref "U8") (pin "34") (pinfunction "U0RXD_34") (pintype "input"))
    )
    (net (code "24") (name "/SCLK") (class "Default")
      (node (ref "CARD1") (pin "5") (pinfunction "CLX_5") (pintype "input"))
      (node (ref "FPC2") (pin "13") (pinfunction "13_13") (pintype "input"))
      (node (ref "R19") (pin "2") (pinfunction "2_2") (pintype "input"))
      (node (ref "U8") (pin "30") (pinfunction "IO18_30") (pintype "input"))
    )
    (net (code "25") (name "/SD_SS") (class "Default")
      (node (ref "CARD1") (pin "2") (pinfunction "CD/DAT3_2") (pintype "input"))
      (node (ref "R21") (pin "2") (pinfunction "2_2") (pintype "input"))
      (node (ref "U8") (pin "23") (pinfunction "IO15_23") (pintype "input"))
    )
    (net (code "26") (name "/TXD0") (class "Default")
      (node (ref "R10") (pin "1") (pinfunction "1_1") (pintype "input"))
      (node (ref "U4") (pin "3") (pinfunction "RXD_3") (pintype "input"))
      (node (ref "U8") (pin "35") (pinfunction "U0TXD_35") (pintype "input"))
    )
    (net (code "27") (name "3V3") (class "Default")
      (node (ref "C16") (pin "1") (pinfunction "1_1") (pintype "input"))
      (node (ref "C17") (pin "1") (pinfunction "1_1") (pintype "input"))
      (node (ref "C19") (pin "1") (pinfunction "1_1") (pintype "input"))
      (node (ref "C21") (pin "1") (pinfunction "1_1") (pintype "input"))
      (node (ref "CARD1") (pin "4") (pinfunction "VDD_4") (pintype "input"))
      (node (ref "FPC2") (pin "15") (pinfunction "15_15") (pintype "input"))
      (node (ref "FPC2") (pin "16") (pinfunction "16_16") (pintype "input"))
      (node (ref "L1") (pin "1") (pinfunction "1_1") (pintype "input"))
      (node (ref "R10") (pin "2") (pinfunction "2_2") (pintype "input"))
      (node (ref "R11") (pin "2") (pinfunction "2_2") (pintype "input"))
      (node (ref "R12") (pin "2") (pinfunction "2_2") (pintype "input"))
      (node (ref "R18") (pin "1") (pinfunction "1_1") (pintype "input"))
      (node (ref "R19") (pin "1") (pinfunction "1_1") (pintype "input"))
      (node (ref "R20") (pin "1") (pinfunction "1_1") (pintype "input"))
      (node (ref "R21") (pin "1") (pinfunction "1_1") (pintype "input"))
      (node (ref "R22") (pin "1") (pinfunction "1_1") (pintype "input"))
      (node (ref "R23") (pin "1") (pinfunction "1_1") (pintype "input"))
      (node (ref "R24") (pin "1") (pinfunction "1_1") (pintype "input"))
      (node (ref "R8") (pin "2") (pinfunction "2_2") (pintype "input"))
      (node (ref "R9") (pin "2") (pinfunction "2_2") (pintype "input"))
      (node (ref "S1") (pin "5") (pinfunction "VDD_5") (pintype "unspecified"))
      (node (ref "U4") (pin "16") (pinfunction "VCC_16") (pintype "input"))
      (node (ref "U4") (pin "4") (pinfunction "V3_4") (pintype "input"))
      (node (ref "U8") (pin "2") (pinfunction "3V3_2") (pintype "input"))
    )
    (net (code "28") (name "GND") (class "Default")
      (node (ref "C1") (pin "1") (pinfunction "1_1") (pintype "input"))
      (node (ref "C10") (pin "2") (pinfunction "2_2") (pintype "input"))
      (node (ref "C11") (pin "2") (pinfunction "2_2") (pintype "input"))
      (node (ref "C12") (pin "2") (pinfunction "2_2") (pintype "input"))
      (node (ref "C13") (pin "2") (pinfunction "2_2") (pintype "input"))
      (node (ref "C14") (pin "2") (pinfunction "2_2") (pintype "input"))
      (node (ref "C15") (pin "2") (pinfunction "2_2") (pintype "input"))
      (node (ref "C16") (pin "2") (pinfunction "2_2") (pintype "input"))
      (node (ref "C17") (pin "2") (pinfunction "2_2") (pintype "input"))
      (node (ref "C19") (pin "2") (pinfunction "2_2") (pintype "input"))
      (node (ref "C20") (pin "2") (pinfunction "2_2") (pintype "input"))
      (node (ref "C21") (pin "2") (pinfunction "2_2") (pintype "input"))
      (node (ref "C22") (pin "2") (pinfunction "2_2") (pintype "input"))
      (node (ref "C23") (pin "2") (pinfunction "2_2") (pintype "input"))
      (node (ref "C24") (pin "2") (pinfunction "2_2") (pintype "input"))
      (node (ref "C5") (pin "1") (pinfunction "1_1") (pintype "input"))
      (node (ref "C6") (pin "1") (pinfunction "1_1") (pintype "input"))
      (node (ref "C7") (pin "2") (pinfunction "2_2") (pintype "input"))
      (node (ref "C8") (pin "2") (pinfunction "2_2") (pintype "input"))
      (node (ref "C9") (pin "2") (pinfunction "2_2") (pintype "input"))
      (node (ref "CARD1") (pin "10") (pinfunction "SHELL_10") (pintype "input"))
      (node (ref "CARD1") (pin "11") (pinfunction "SHELL_11") (pintype "input"))
      (node (ref "CARD1") (pin "12") (pinfunction "SHELL_12") (pintype "input"))
      (node (ref "CARD1") (pin "13") (pinfunction "SHELL_13") (pintype "input"))
      (node (ref "CARD1") (pin "6") (pinfunction "VSS_6") (pintype "input"))
      (node (ref "D1") (pin "1") (pinfunction "1_1") (pintype "input"))
      (node (ref "D6") (pin "1") (pinfunction "K_1") (pintype "input"))
      (node (ref "FPC2") (pin "17") (pinfunction "17_17") (pintype "input"))
      (node (ref "FPC2") (pin "25") (pinfunction "25_25") (pintype "input"))
      (node (ref "FPC2") (pin "26") (pinfunction "26_26") (pintype "input"))
      (node (ref "FPC2") (pin "8") (pinfunction "8_8") (pintype "input"))
      (node (ref "KEY1") (pin "1") (pinfunction "1_1") (pintype "input"))
      (node (ref "KEY1") (pin "3") (pinfunction "3_3") (pintype "input"))
      (node (ref "KEY1") (pin "4") (pinfunction "4_4") (pintype "input"))
      (node (ref "KEY2") (pin "1") (pinfunction "1_1") (pintype "input"))
      (node (ref "KEY2") (pin "3") (pinfunction "3_3") (pintype "input"))
      (node (ref "KEY2") (pin "4") (pinfunction "4_4") (pintype "input"))
      (node (ref "KEY3") (pin "1") (pinfunction "1_1") (pintype "input"))
      (node (ref "KEY3") (pin "3") (pinfunction "3_3") (pintype "input"))
      (node (ref "KEY3") (pin "4") (pinfunction "4_4") (pintype "input"))
      (node (ref "Q2") (pin "2") (pinfunction "S_2") (pintype "input"))
      (node (ref "Q7") (pin "2") (pinfunction "E_2") (pintype "input"))
      (node (ref "R1") (pin "1") (pinfunction "1_1") (pintype "input"))
      (node (ref "R13") (pin "1") (pinfunction "1_1") (pintype "input"))
      (node (ref "R14") (pin "1") (pinfunction "1_1") (pintype "input"))
      (node (ref "R16") (pin "1") (pinfunction "1_1") (pintype "input"))
      (node (ref "R3") (pin "1") (pinfunction "1_1") (pintype "input"))
      (node (ref "R5") (pin "1") (pinfunction "1_1") (pintype "input"))
      (node (ref "RESET1") (pin "2") (pinfunction "2_2") (pintype "input"))
      (node (ref "RESET1") (pin "3") (pinfunction "3_3") (pintype "input"))
      (node (ref "RESET1") (pin "4") (pinfunction "4_4") (pintype "input"))
      (node (ref "S1") (pin "2") (pinfunction "ADDR_2") (pintype "unspecified"))
      (node (ref "S1") (pin "7") (pinfunction "R_7") (pintype "unspecified"))
      (node (ref "S1") (pin "8") (pinfunction "VSS_8") (pintype "unspecified"))
      (node (ref "S1") (pin "9") (pinfunction "EPAD_9") (pintype "unspecified"))
      (node (ref "U1") (pin "1") (pinfunction "TEMP_1") (pintype "input"))
      (node (ref "U1") (pin "3") (pinfunction "GND_3") (pintype "input"))
      (node (ref "U1") (pin "9") (pinfunction "EP_9") (pintype "input"))
      (node (ref "U7") (pin "11") (pinfunction "GND_11") (pintype "input"))
      (node (ref "U7") (pin "7") (pinfunction "FOE_7") (pintype "input"))
      (node (ref "U8") (pin "1") (pinfunction "GND_1") (pintype "input"))
      (node (ref "U8") (pin "15") (pinfunction "GND_15") (pintype "input"))
      (node (ref "U8") (pin "38") (pinfunction "GND_38") (pintype "input"))
      (node (ref "U8") (pin "39") (pinfunction "EP_39") (pintype "input"))
      (node (ref "USB1") (pin "1") (pinfunction "SHELL_1") (pintype "input"))
      (node (ref "USB1") (pin "2") (pinfunction "SHELL_2") (pintype "input"))
      (node (ref "USB1") (pin "3") (pinfunction "SHELL_3") (pintype "input"))
      (node (ref "USB1") (pin "4") (pinfunction "SHELL_4") (pintype "input"))
      (node (ref "USB1") (pin "A1B12") (pinfunction "GND_A1B12") (pintype "input"))
      (node (ref "USB1") (pin "B1A12") (pinfunction "GND_B1A12") (pintype "input"))
    )
    (net (code "29") (name "Net-(BUZZER1-Pad1)") (class "Default")
      (node (ref "BUZZER1") (pin "1") (pinfunction "1_1") (pintype "input"))
      (node (ref "R17") (pin "2") (pinfunction "2_2") (pintype "input"))
    )
    (net (code "30") (name "Net-(C7-Pad1)") (class "Default")
      (node (ref "C7") (pin "1") (pinfunction "1_1") (pintype "input"))
      (node (ref "FPC2") (pin "4") (pinfunction "4_4") (pintype "input"))
    )
    (net (code "31") (name "Net-(C8-Pad1)") (class "Default")
      (node (ref "C8") (pin "1") (pinfunction "1_1") (pintype "input"))
      (node (ref "FPC2") (pin "5") (pinfunction "5_5") (pintype "input"))
    )
    (net (code "32") (name "Net-(C9-Pad1)") (class "Default")
      (node (ref "C9") (pin "1") (pinfunction "1_1") (pintype "input"))
      (node (ref "FPC2") (pin "18") (pinfunction "18_18") (pintype "input"))
    )
    (net (code "33") (name "Net-(C10-Pad1)") (class "Default")
      (node (ref "C10") (pin "1") (pinfunction "1_1") (pintype "input"))
      (node (ref "FPC2") (pin "19") (pinfunction "19_19") (pintype "input"))
    )
    (net (code "34") (name "Net-(C11-Pad1)") (class "Default")
      (node (ref "C11") (pin "1") (pinfunction "1_1") (pintype "input"))
      (node (ref "FPC2") (pin "20") (pinfunction "20_20") (pintype "input"))
    )
    (net (code "35") (name "Net-(C13-Pad1)") (class "Default")
      (node (ref "C13") (pin "1") (pinfunction "1_1") (pintype "input"))
      (node (ref "FPC2") (pin "22") (pinfunction "22_22") (pintype "input"))
    )
    (net (code "36") (name "Net-(C15-Pad1)") (class "Default")
      (node (ref "C15") (pin "1") (pinfunction "1_1") (pintype "input"))
      (node (ref "FPC2") (pin "24") (pinfunction "24_24") (pintype "input"))
    )
    (net (code "37") (name "Net-(CHRG1-A)") (class "Default")
      (node (ref "CHRG1") (pin "1") (pinfunction "A_1") (pintype "input"))
      (node (ref "DONE1") (pin "1") (pinfunction "A_1") (pintype "input"))
      (node (ref "R4") (pin "1") (pinfunction "1_1") (pintype "input"))
    )
    (net (code "38") (name "Net-(CHRG1-C)") (class "Default")
      (node (ref "CHRG1") (pin "2") (pinfunction "C_2") (pintype "input"))
      (node (ref "U1") (pin "7") (pinfunction "CHRG_7") (pintype "input"))
    )
    (net (code "39") (name "Net-(D5-K)") (class "Default")
      (node (ref "C5") (pin "2") (pinfunction "2_2") (pintype "input"))
      (node (ref "C6") (pin "2") (pinfunction "2_2") (pintype "input"))
      (node (ref "D5") (pin "1") (pinfunction "K_1") (pintype "input"))
      (node (ref "U7") (pin "6") (pinfunction "VDD_6") (pintype "input"))
    )
    (net (code "40") (name "Net-(D6-A)") (class "Default")
      (node (ref "C18") (pin "1") (pinfunction "1_1") (pintype "input"))
      (node (ref "D6") (pin "2") (pinfunction "A_2") (pintype "input"))
      (node (ref "D7") (pin "1") (pinfunction "K_1") (pintype "input"))
    )
    (net (code "41") (name "Net-(D8-A)") (class "Default")
      (node (ref "C18") (pin "2") (pinfunction "2_2") (pintype "input"))
      (node (ref "D8") (pin "2") (pinfunction "A_2") (pintype "input"))
      (node (ref "L1") (pin "2") (pinfunction "2_2") (pintype "input"))
      (node (ref "Q3") (pin "3") (pinfunction "D_3") (pintype "input"))
    )
    (net (code "42") (name "Net-(DONE1-C)") (class "Default")
      (node (ref "DONE1") (pin "2") (pinfunction "C_2") (pintype "input"))
      (node (ref "U1") (pin "6") (pinfunction "STDBY_6") (pintype "input"))
    )
    (net (code "43") (name "Net-(Q2-D)") (class "Default")
      (node (ref "Q2") (pin "3") (pinfunction "D_3") (pintype "input"))
      (node (ref "U4") (pin "1") (pinfunction "GND_1") (pintype "input"))
    )
    (net (code "44") (name "Net-(Q4-B)") (class "Default")
      (node (ref "Q4") (pin "1") (pinfunction "B_1") (pintype "input"))
      (node (ref "R7") (pin "1") (pinfunction "1_1") (pintype "input"))
    )
    (net (code "45") (name "Net-(Q4-E)") (class "Default")
      (node (ref "Q4") (pin "2") (pinfunction "E_2") (pintype "input"))
      (node (ref "R6") (pin "2") (pinfunction "2_2") (pintype "input"))
      (node (ref "U4") (pin "13") (pinfunction "DTR#_13") (pintype "input"))
    )
    (net (code "46") (name "Net-(Q5-B)") (class "Default")
      (node (ref "Q5") (pin "1") (pinfunction "B_1") (pintype "input"))
      (node (ref "R6") (pin "1") (pinfunction "1_1") (pintype "input"))
    )
    (net (code "47") (name "Net-(Q5-E)") (class "Default")
      (node (ref "Q5") (pin "2") (pinfunction "E_2") (pintype "input"))
      (node (ref "R7") (pin "2") (pinfunction "2_2") (pintype "input"))
      (node (ref "U4") (pin "14") (pinfunction "RTS#_14") (pintype "input"))
    )
    (net (code "48") (name "Net-(Q7-B)") (class "Default")
      (node (ref "Q7") (pin "1") (pinfunction "B_1") (pintype "input"))
      (node (ref "R15") (pin "1") (pinfunction "1_1") (pintype "input"))
      (node (ref "R16") (pin "2") (pinfunction "2_2") (pintype "input"))
    )
    (net (code "49") (name "Net-(Q7-C)") (class "Default")
      (node (ref "BUZZER1") (pin "2") (pinfunction "2_2") (pintype "input"))
      (node (ref "Q7") (pin "3") (pinfunction "C_3") (pintype "input"))
    )
    (net (code "50") (name "Net-(U1-PROG)") (class "Default")
      (node (ref "R3") (pin "2") (pinfunction "2_2") (pintype "input"))
      (node (ref "U1") (pin "2") (pinfunction "PROG_2") (pintype "input"))
    )
    (net (code "51") (name "Net-(USB1-CC1)") (class "Default")
      (node (ref "R1") (pin "2") (pinfunction "2_2") (pintype "input"))
      (node (ref "USB1") (pin "A5") (pinfunction "CC1_A5") (pintype "input"))
      (node (ref "USB1") (pin "B5") (pinfunction "CC2_B5") (pintype "input"))
    )
    (net (code "52") (name "unconnected-(C2-Pad1)") (class "Default")
      (node (ref "C2") (pin "1") (pinfunction "1_1") (pintype "input"))
    )
    (net (code "53") (name "unconnected-(C2-Pad2)") (class "Default")
      (node (ref "C2") (pin "2") (pinfunction "2_2") (pintype "input"))
    )
    (net (code "54") (name "unconnected-(C3-Pad1)") (class "Default")
      (node (ref "C3") (pin "1") (pinfunction "1_1") (pintype "input"))
    )
    (net (code "55") (name "unconnected-(C3-Pad2)") (class "Default")
      (node (ref "C3") (pin "2") (pinfunction "2_2") (pintype "input"))
    )
    (net (code "56") (name "unconnected-(C4-Pad1)") (class "Default")
      (node (ref "C4") (pin "1") (pinfunction "1_1") (pintype "input"))
    )
    (net (code "57") (name "unconnected-(C4-Pad2)") (class "Default")
      (node (ref "C4") (pin "2") (pinfunction "2_2") (pintype "input"))
    )
    (net (code "58") (name "unconnected-(CARD1-CD-Pad9)") (class "Default")
      (node (ref "CARD1") (pin "9") (pinfunction "CD_9") (pintype "input+no_connect"))
    )
    (net (code "59") (name "unconnected-(CARD1-DAT1-Pad8)") (class "Default")
      (node (ref "CARD1") (pin "8") (pinfunction "DAT1_8") (pintype "input+no_connect"))
    )
    (net (code "60") (name "unconnected-(CARD1-DAT2-Pad1)") (class "Default")
      (node (ref "CARD1") (pin "1") (pinfunction "DAT2_1") (pintype "input+no_connect"))
    )
    (net (code "61") (name "unconnected-(D4-A-Pad2)") (class "Default")
      (node (ref "D4") (pin "2") (pinfunction "A_2") (pintype "input"))
    )
    (net (code "62") (name "unconnected-(D4-C-Pad1)") (class "Default")
      (node (ref "D4") (pin "1") (pinfunction "C_1") (pintype "input"))
    )
    (net (code "63") (name "unconnected-(FPC2-Pad1)") (class "Default")
      (node (ref "FPC2") (pin "1") (pinfunction "1_1") (pintype "input+no_connect"))
    )
    (net (code "64") (name "unconnected-(FPC2-Pad6)") (class "Default")
      (node (ref "FPC2") (pin "6") (pinfunction "6_6") (pintype "input+no_connect"))
    )
    (net (code "65") (name "unconnected-(FPC2-Pad7)") (class "Default")
      (node (ref "FPC2") (pin "7") (pinfunction "7_7") (pintype "input+no_connect"))
    )
    (net (code "66") (name "unconnected-(Q1-D-Pad3)") (class "Default")
      (node (ref "Q1") (pin "3") (pinfunction "D_3") (pintype "input"))
    )
    (net (code "67") (name "unconnected-(Q1-G-Pad1)") (class "Default")
      (node (ref "Q1") (pin "1") (pinfunction "G_1") (pintype "input"))
    )
    (net (code "68") (name "unconnected-(Q1-S-Pad2)") (class "Default")
      (node (ref "Q1") (pin "2") (pinfunction "S_2") (pintype "input"))
    )
    (net (code "69") (name "unconnected-(R2-Pad1)") (class "Default")
      (node (ref "R2") (pin "1") (pinfunction "1_1") (pintype "input"))
    )
    (net (code "70") (name "unconnected-(R2-Pad2)") (class "Default")
      (node (ref "R2") (pin "2") (pinfunction "2_2") (pintype "input"))
    )
    (net (code "71") (name "unconnected-(S1-ALERT-Pad3)") (class "Default")
      (node (ref "S1") (pin "3") (pinfunction "ALERT_3") (pintype "unspecified+no_connect"))
    )
    (net (code "72") (name "unconnected-(S1-NRESET-Pad6)") (class "Default")
      (node (ref "S1") (pin "6") (pinfunction "NRESET_6") (pintype "unspecified+no_connect"))
    )
    (net (code "73") (name "unconnected-(U4-CTS#-Pad9)") (class "Default")
      (node (ref "U4") (pin "9") (pinfunction "CTS#_9") (pintype "input+no_connect"))
    )
    (net (code "74") (name "unconnected-(U4-DCD#-Pad12)") (class "Default")
      (node (ref "U4") (pin "12") (pinfunction "DCD#_12") (pintype "input+no_connect"))
    )
    (net (code "75") (name "unconnected-(U4-DSR#-Pad10)") (class "Default")
      (node (ref "U4") (pin "10") (pinfunction "DSR#_10") (pintype "input+no_connect"))
    )
    (net (code "76") (name "unconnected-(U4-NC.-Pad7)") (class "Default")
      (node (ref "U4") (pin "7") (pinfunction "NC._7") (pintype "input+no_connect"))
    )
    (net (code "77") (name "unconnected-(U4-NC.-Pad8)") (class "Default")
      (node (ref "U4") (pin "8") (pinfunction "NC._8") (pintype "input+no_connect"))
    )
    (net (code "78") (name "unconnected-(U4-R232-Pad15)") (class "Default")
      (node (ref "U4") (pin "15") (pinfunction "R232_15") (pintype "input+no_connect"))
    )
    (net (code "79") (name "unconnected-(U4-RI#-Pad11)") (class "Default")
      (node (ref "U4") (pin "11") (pinfunction "RI#_11") (pintype "input+no_connect"))
    )
    (net (code "80") (name "unconnected-(U7-FOUT-Pad3)") (class "Default")
      (node (ref "U7") (pin "3") (pinfunction "FOUT_3") (pintype "input+no_connect"))
    )
    (net (code "81") (name "unconnected-(U7-INT#-Pad10)") (class "Default")
      (node (ref "U7") (pin "10") (pinfunction "INT#_10") (pintype "input+no_connect"))
    )
    (net (code "82") (name "unconnected-(U7-NC-Pad4)") (class "Default")
      (node (ref "U7") (pin "4") (pinfunction "NC_4") (pintype "input+no_connect"))
    )
    (net (code "83") (name "unconnected-(U7-NC-Pad8)") (class "Default")
      (node (ref "U7") (pin "8") (pinfunction "NC_8") (pintype "input+no_connect"))
    )
    (net (code "84") (name "unconnected-(U7-NC-Pad9)") (class "Default")
      (node (ref "U7") (pin "9") (pinfunction "NC_9") (pintype "input+no_connect"))
    )
    (net (code "85") (name "unconnected-(U7-NC-Pad14)") (class "Default")
      (node (ref "U7") (pin "14") (pinfunction "NC_14") (pintype "input+no_connect"))
    )
    (net (code "86") (name "unconnected-(U7-T1-Pad1)") (class "Default")
      (node (ref "U7") (pin "1") (pinfunction "T1_1") (pintype "input+no_connect"))
    )
    (net (code "87") (name "unconnected-(U7-T2-Pad12)") (class "Default")
      (node (ref "U7") (pin "12") (pinfunction "T2_12") (pintype "input+no_connect"))
    )
    (net (code "88") (name "unconnected-(U7-TEST-Pad5)") (class "Default")
      (node (ref "U7") (pin "5") (pinfunction "TEST_5") (pintype "input+no_connect"))
    )
    (net (code "89") (name "unconnected-(U8-CLK-Pad20)") (class "Default")
      (node (ref "U8") (pin "20") (pinfunction "CLK_20") (pintype "input+no_connect"))
    )
    (net (code "90") (name "unconnected-(U8-CMD-Pad19)") (class "Default")
      (node (ref "U8") (pin "19") (pinfunction "CMD_19") (pintype "input+no_connect"))
    )
    (net (code "91") (name "unconnected-(U8-IO2-Pad24)") (class "Default")
      (node (ref "U8") (pin "24") (pinfunction "IO2_24") (pintype "input+no_connect"))
    )
    (net (code "92") (name "unconnected-(U8-IO12-Pad14)") (class "Default")
      (node (ref "U8") (pin "14") (pinfunction "IO12_14") (pintype "input+no_connect"))
    )
    (net (code "93") (name "unconnected-(U8-IO13-Pad16)") (class "Default")
      (node (ref "U8") (pin "16") (pinfunction "IO13_16") (pintype "input+no_connect"))
    )
    (net (code "94") (name "unconnected-(U8-IO14-Pad13)") (class "Default")
      (node (ref "U8") (pin "13") (pinfunction "IO14_13") (pintype "input+no_connect"))
    )
    (net (code "95") (name "unconnected-(U8-IO32-Pad8)") (class "Default")
      (node (ref "U8") (pin "8") (pinfunction "IO32_8") (pintype "input+no_connect"))
    )
    (net (code "96") (name "unconnected-(U8-IO34-Pad6)") (class "Default")
      (node (ref "U8") (pin "6") (pinfunction "IO34_6") (pintype "input+no_connect"))
    )
    (net (code "97") (name "unconnected-(U8-IO35-Pad7)") (class "Default")
      (node (ref "U8") (pin "7") (pinfunction "IO35_7") (pintype "input+no_connect"))
    )
    (net (code "98") (name "unconnected-(U8-NC-Pad32)") (class "Default")
      (node (ref "U8") (pin "32") (pinfunction "NC_32") (pintype "input+no_connect"))
    )
    (net (code "99") (name "unconnected-(U8-SD2-Pad17)") (class "Default")
      (node (ref "U8") (pin "17") (pinfunction "SD2_17") (pintype "input+no_connect"))
    )
    (net (code "100") (name "unconnected-(U8-SD3-Pad18)") (class "Default")
      (node (ref "U8") (pin "18") (pinfunction "SD3_18") (pintype "input+no_connect"))
    )
    (net (code "101") (name "unconnected-(U8-SDI-Pad22)") (class "Default")
      (node (ref "U8") (pin "22") (pinfunction "SDI_22") (pintype "input+no_connect"))
    )
    (net (code "102") (name "unconnected-(U8-SDO-Pad21)") (class "Default")
      (node (ref "U8") (pin "21") (pinfunction "SDO_21") (pintype "input+no_connect"))
    )
    (net (code "103") (name "unconnected-(U8-SENSOR_VN-Pad5)") (class "Default")
      (node (ref "U8") (pin "5") (pinfunction "SENSOR_VN_5") (pintype "input+no_connect"))
    )
    (net (code "104") (name "unconnected-(U8-SENSOR_VP-Pad4)") (class "Default")
      (node (ref "U8") (pin "4") (pinfunction "SENSOR_VP_4") (pintype "input+no_connect"))
    )
    (net (code "105") (name "unconnected-(U17-Pad1)") (class "Default")
      (node (ref "U17") (pin "1") (pinfunction "1_1") (pintype "unspecified"))
    )
    (net (code "106") (name "unconnected-(U17-Pad2)") (class "Default")
      (node (ref "U17") (pin "2") (pinfunction "2_2") (pintype "unspecified"))
    )
    (net (code "107") (name "unconnected-(U17-Pad3)") (class "Default")
      (node (ref "U17") (pin "3") (pinfunction "3_3") (pintype "unspecified"))
    )
    (net (code "108") (name "unconnected-(USB1-SBU1-PadA8)") (class "Default")
      (node (ref "USB1") (pin "A8") (pinfunction "SBU1_A8") (pintype "input+no_connect"))
    )
    (net (code "109") (name "unconnected-(USB1-SBU2-PadB8)") (class "Default")
      (node (ref "USB1") (pin "B8") (pinfunction "SBU2_B8") (pintype "input+no_connect"))
    )
  )
)
